# keyInput.net
KiCad netlist of a schematic drawn in Altium Designer
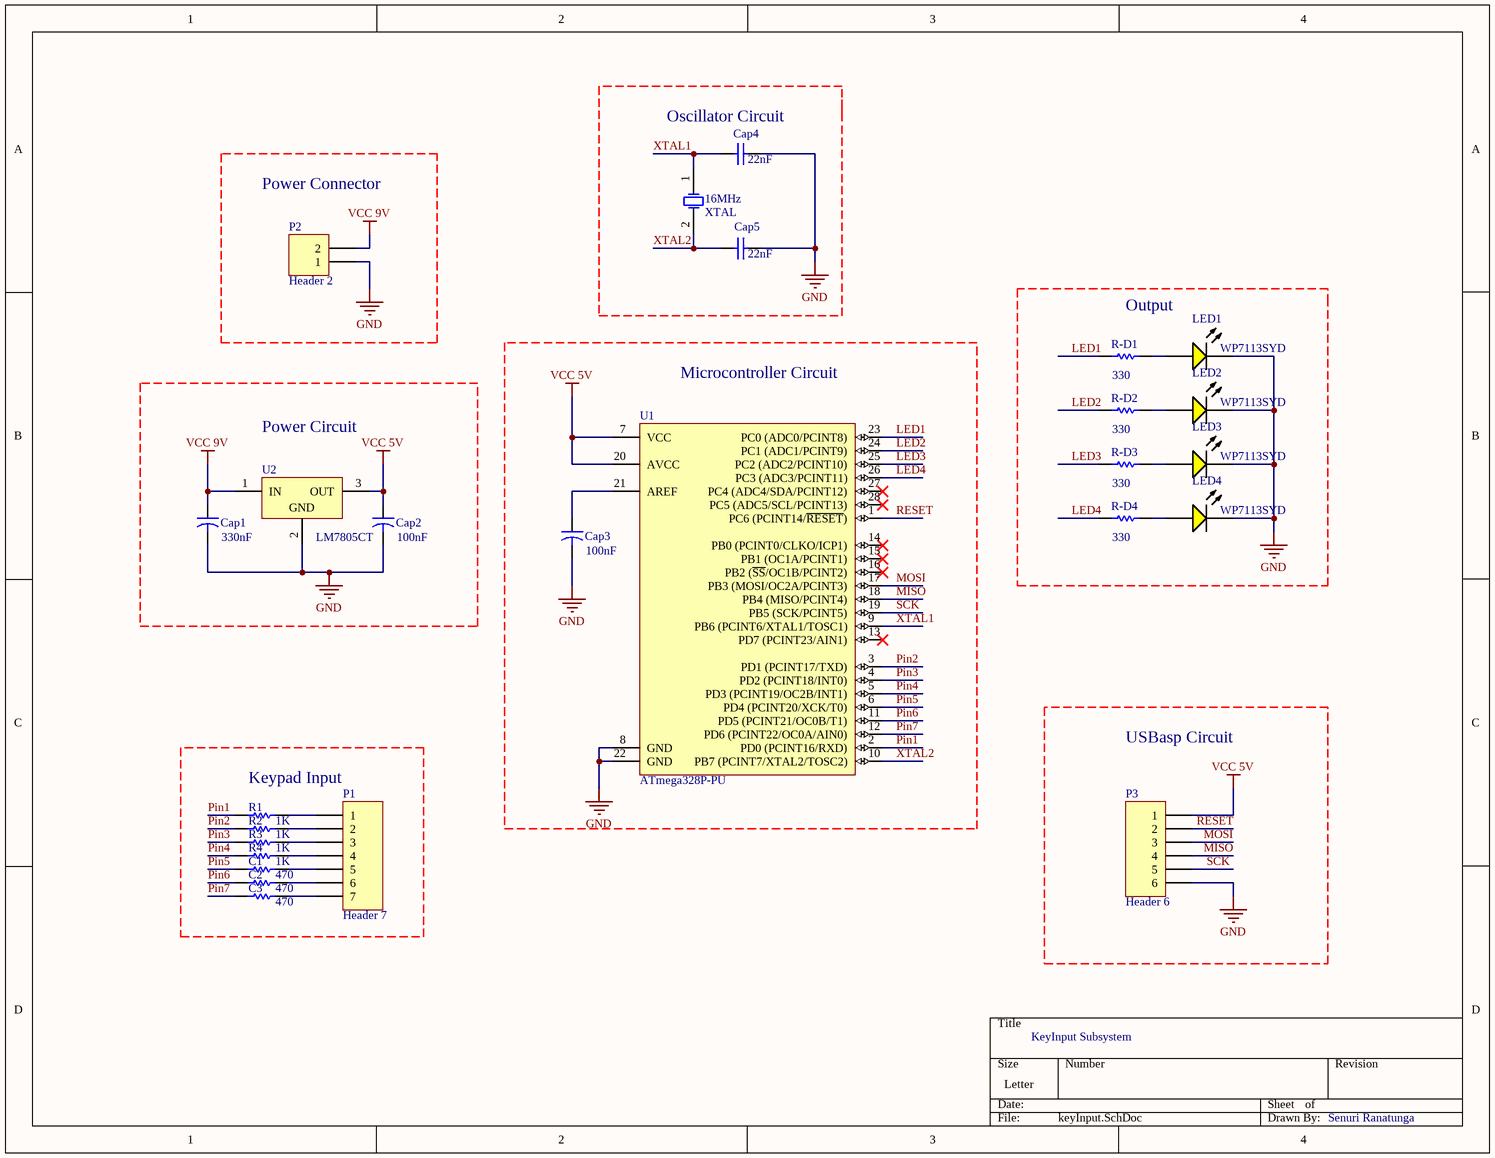
[diagram p0: keyInput.SchDoc]

(export (version "E")
  (design (tool "Eeschema 10.0.6"))
  (components
    (comp (ref "16MHz")
      (value "XTAL")
      (footprint "R38")
      (description "Crystal Oscillator")
      (fields (field (name "PUBLISHER") "Altium Limited"))
      (libsource (lib "Miscellaneous Devices") (part "XTAL"))
    )
    (comp (ref "C1")
      (value "470")
      (footprint "AXIAL-0.3")
      (description "Resistor")
      (fields (field (name "PUBLISHER") "Altium Limited"))
      (libsource (lib "Miscellaneous Devices") (part "Res1"))
    )
    (comp (ref "C2")
      (value "470")
      (footprint "AXIAL-0.3")
      (description "Resistor")
      (fields (field (name "PUBLISHER") "Altium Limited"))
      (libsource (lib "Miscellaneous Devices") (part "Res1"))
    )
    (comp (ref "C3")
      (value "470")
      (footprint "AXIAL-0.3")
      (description "Resistor")
      (fields (field (name "PUBLISHER") "Altium Limited"))
      (libsource (lib "Miscellaneous Devices") (part "Res1"))
    )
    (comp (ref "Cap1")
      (value "330nF")
      (footprint "CAPR5-4X5")
      (description "Capacitor")
      (fields (field (name "PUBLISHER") "Altium Limited"))
      (libsource (lib "Miscellaneous Devices") (part "Cap2"))
    )
    (comp (ref "Cap2")
      (value "100nF")
      (footprint "CAPR5-4X5")
      (description "Capacitor")
      (fields (field (name "PUBLISHER") "Altium Limited"))
      (libsource (lib "Miscellaneous Devices") (part "Cap2"))
    )
    (comp (ref "Cap3")
      (value "100nF")
      (footprint "CAPR5-4X5")
      (description "Capacitor")
      (fields (field (name "PUBLISHER") "Altium Limited"))
      (libsource (lib "Miscellaneous Devices") (part "Cap2"))
    )
    (comp (ref "Cap4")
      (value "22nF")
      (footprint "RAD-0.3")
      (description "Capacitor")
      (fields (field (name "PUBLISHER") "Altium Limited"))
      (libsource (lib "Miscellaneous Devices") (part "Cap"))
    )
    (comp (ref "Cap5")
      (value "22nF")
      (footprint "RAD-0.3")
      (description "Capacitor")
      (fields (field (name "PUBLISHER") "Altium Limited"))
      (libsource (lib "Miscellaneous Devices") (part "Cap"))
    )
    (comp (ref "LED1")
      (value "WP7113SYD")
      (footprint "KING-WP7113SYD_V")
      (description "The Super Bright Yellow Device, 2 V, -40 to 85 degC, 2-Pin THD, RoHS, Tape and Reel")
      (fields (field (name "TOLERANCE") "1%"))
      (libsource (lib "Altium Content Vault") (part "LED-YELLOW-AK-2"))
    )
    (comp (ref "LED2")
      (value "WP7113SYD")
      (footprint "KING-WP7113SYD_V")
      (description "The Super Bright Yellow Device, 2 V, -40 to 85 degC, 2-Pin THD, RoHS, Tape and Reel")
      (fields (field (name "TOLERANCE") "1%"))
      (libsource (lib "Altium Content Vault") (part "LED-YELLOW-AK-2"))
    )
    (comp (ref "LED3")
      (value "WP7113SYD")
      (footprint "KING-WP7113SYD_V")
      (description "The Super Bright Yellow Device, 2 V, -40 to 85 degC, 2-Pin THD, RoHS, Tape and Reel")
      (fields (field (name "TOLERANCE") "1%"))
      (libsource (lib "Altium Content Vault") (part "LED-YELLOW-AK-2"))
    )
    (comp (ref "LED4")
      (value "WP7113SYD")
      (footprint "KING-WP7113SYD_V")
      (description "The Super Bright Yellow Device, 2 V, -40 to 85 degC, 2-Pin THD, RoHS, Tape and Reel")
      (fields (field (name "TOLERANCE") "1%"))
      (libsource (lib "Altium Content Vault") (part "LED-YELLOW-AK-2"))
    )
    (comp (ref "P1")
      (value "Header 7")
      (footprint "HDR1X7")
      (description "Header, 7-Pin")
      (fields (field (name "PUBLISHER") "Altium Limited"))
      (libsource (lib "Miscellaneous Connectors") (part "Header 7"))
    )
    (comp (ref "P2")
      (value "Header 2")
      (footprint "HDR1X2")
      (description "Header, 2-Pin")
      (fields (field (name "PUBLISHER") "Altium Limited"))
      (libsource (lib "Miscellaneous Connectors") (part "Header 2"))
    )
    (comp (ref "P3")
      (value "Header 6")
      (footprint "HDR1X6")
      (description "Header, 6-Pin")
      (fields (field (name "PUBLISHER") "Altium Limited"))
      (libsource (lib "Miscellaneous Connectors") (part "Header 6"))
    )
    (comp (ref "R-D1")
      (value "330")
      (footprint "AXIAL-0.3")
      (description "Resistor")
      (fields (field (name "PUBLISHER") "Altium Limited"))
      (libsource (lib "Miscellaneous Devices") (part "Res1"))
    )
    (comp (ref "R-D2")
      (value "330")
      (footprint "AXIAL-0.3")
      (description "Resistor")
      (fields (field (name "PUBLISHER") "Altium Limited"))
      (libsource (lib "Miscellaneous Devices") (part "Res1"))
    )
    (comp (ref "R-D3")
      (value "330")
      (footprint "AXIAL-0.3")
      (description "Resistor")
      (fields (field (name "PUBLISHER") "Altium Limited"))
      (libsource (lib "Miscellaneous Devices") (part "Res1"))
    )
    (comp (ref "R-D4")
      (value "330")
      (footprint "AXIAL-0.3")
      (description "Resistor")
      (fields (field (name "PUBLISHER") "Altium Limited"))
      (libsource (lib "Miscellaneous Devices") (part "Res1"))
    )
    (comp (ref "R1")
      (value "1K")
      (footprint "AXIAL-0.3")
      (description "Resistor")
      (fields (field (name "PUBLISHER") "Altium Limited"))
      (libsource (lib "Miscellaneous Devices") (part "Res1"))
    )
    (comp (ref "R2")
      (value "1K")
      (footprint "AXIAL-0.3")
      (description "Resistor")
      (fields (field (name "PUBLISHER") "Altium Limited"))
      (libsource (lib "Miscellaneous Devices") (part "Res1"))
    )
    (comp (ref "R3")
      (value "1K")
      (footprint "AXIAL-0.3")
      (description "Resistor")
      (fields (field (name "PUBLISHER") "Altium Limited"))
      (libsource (lib "Miscellaneous Devices") (part "Res1"))
    )
    (comp (ref "R4")
      (value "1K")
      (footprint "AXIAL-0.3")
      (description "Resistor")
      (fields (field (name "PUBLISHER") "Altium Limited"))
      (libsource (lib "Miscellaneous Devices") (part "Res1"))
    )
    (comp (ref "U1")
      (value "ATmega328P-PU")
      (footprint "28P3")
      (libsource (lib "Altium Content Vault") (part "MC-8B-ATM48-IL28"))
    )
    (comp (ref "U2")
      (value "LM7805CT")
      (footprint "FAIR-TO-220-3")
      (description "Positive Voltage Regulator, 5 V, 1 A, -40 to 125 degC, 3-Pin TO-220, RoHS, Tube")
      (fields (field (name "MANUFACTURER") "FairchildSemiconductor"))
      (libsource (lib "Altium Content Vault") (part "FAIR-LM7805CT-TO220-3"))
    )
  )
  (nets
    (net (code "1") (name "/LED1") (class "Default")
      (node (ref "R-D1") (pin "1") (pinfunction "1_1") (pintype "passive"))
      (node (ref "U1") (pin "23") (pinfunction "PC0_(ADC0/PCINT8)_23") (pintype "bidirectional"))
    )
    (net (code "2") (name "/LED2") (class "Default")
      (node (ref "R-D2") (pin "1") (pinfunction "1_1") (pintype "passive"))
      (node (ref "U1") (pin "24") (pinfunction "PC1_(ADC1/PCINT9)_24") (pintype "bidirectional"))
    )
    (net (code "3") (name "/LED3") (class "Default")
      (node (ref "R-D3") (pin "1") (pinfunction "1_1") (pintype "passive"))
      (node (ref "U1") (pin "25") (pinfunction "PC2_(ADC2/PCINT10)_25") (pintype "bidirectional"))
    )
    (net (code "4") (name "/LED4") (class "Default")
      (node (ref "R-D4") (pin "1") (pinfunction "1_1") (pintype "passive"))
      (node (ref "U1") (pin "26") (pinfunction "PC3_(ADC3/PCINT11)_26") (pintype "bidirectional"))
    )
    (net (code "5") (name "/MISO") (class "Default")
      (node (ref "P3") (pin "4") (pinfunction "4_4") (pintype "passive"))
      (node (ref "U1") (pin "18") (pinfunction "PB4_(MISO/PCINT4)_18") (pintype "bidirectional"))
    )
    (net (code "6") (name "/MOSI") (class "Default")
      (node (ref "P3") (pin "3") (pinfunction "3_3") (pintype "passive"))
      (node (ref "U1") (pin "17") (pinfunction "PB3_(MOSI/OC2A/PCINT3)_17") (pintype "bidirectional"))
    )
    (net (code "7") (name "/Pin1") (class "Default")
      (node (ref "R1") (pin "2") (pinfunction "2_2") (pintype "passive"))
      (node (ref "U1") (pin "2") (pinfunction "PD0_(PCINT16/RXD)_2") (pintype "bidirectional"))
    )
    (net (code "8") (name "/Pin2") (class "Default")
      (node (ref "R2") (pin "1") (pinfunction "1_1") (pintype "passive"))
      (node (ref "U1") (pin "3") (pinfunction "PD1_(PCINT17/TXD)_3") (pintype "bidirectional"))
    )
    (net (code "9") (name "/Pin3") (class "Default")
      (node (ref "R3") (pin "1") (pinfunction "1_1") (pintype "passive"))
      (node (ref "U1") (pin "4") (pinfunction "PD2_(PCINT18/INT0)_4") (pintype "bidirectional"))
    )
    (net (code "10") (name "/Pin4") (class "Default")
      (node (ref "R4") (pin "2") (pinfunction "2_2") (pintype "passive"))
      (node (ref "U1") (pin "5") (pinfunction "PD3_(PCINT19/OC2B/INT1)_5") (pintype "bidirectional"))
    )
    (net (code "11") (name "/Pin5") (class "Default")
      (node (ref "C1") (pin "1") (pinfunction "1_1") (pintype "passive"))
      (node (ref "U1") (pin "6") (pinfunction "PD4_(PCINT20/XCK/T0)_6") (pintype "bidirectional"))
    )
    (net (code "12") (name "/Pin6") (class "Default")
      (node (ref "C2") (pin "1") (pinfunction "1_1") (pintype "passive"))
      (node (ref "U1") (pin "11") (pinfunction "PD5_(PCINT21/OC0B/T1)_11") (pintype "bidirectional"))
    )
    (net (code "13") (name "/Pin7") (class "Default")
      (node (ref "C3") (pin "1") (pinfunction "1_1") (pintype "passive"))
      (node (ref "U1") (pin "12") (pinfunction "PD6_(PCINT22/OC0A/AIN0)_12") (pintype "bidirectional"))
    )
    (net (code "14") (name "/RESET") (class "Default")
      (node (ref "P3") (pin "2") (pinfunction "2_2") (pintype "passive"))
      (node (ref "U1") (pin "1") (pinfunction "PC6_(PCINT14/~{RESET})_1") (pintype "bidirectional"))
    )
    (net (code "15") (name "/SCK") (class "Default")
      (node (ref "P3") (pin "5") (pinfunction "5_5") (pintype "passive"))
      (node (ref "U1") (pin "19") (pinfunction "PB5_(SCK/PCINT5)_19") (pintype "bidirectional"))
    )
    (net (code "16") (name "/XTAL1") (class "Default")
      (node (ref "16MHz") (pin "1") (pinfunction "OSC1_1") (pintype "passive"))
      (node (ref "Cap4") (pin "1") (pinfunction "1_1") (pintype "passive"))
      (node (ref "U1") (pin "9") (pinfunction "PB6_(PCINT6/XTAL1/TOSC1)_9") (pintype "bidirectional"))
    )
    (net (code "17") (name "/XTAL2") (class "Default")
      (node (ref "16MHz") (pin "2") (pinfunction "OSC2_2") (pintype "passive"))
      (node (ref "Cap5") (pin "1") (pinfunction "1_1") (pintype "passive"))
      (node (ref "U1") (pin "10") (pinfunction "PB7_(PCINT7/XTAL2/TOSC2)_10") (pintype "bidirectional"))
    )
    (net (code "18") (name "GND") (class "Default")
      (node (ref "Cap1") (pin "2") (pinfunction "2_2") (pintype "passive"))
      (node (ref "Cap2") (pin "2") (pinfunction "2_2") (pintype "passive"))
      (node (ref "Cap3") (pin "2") (pinfunction "2_2") (pintype "passive"))
      (node (ref "Cap4") (pin "2") (pinfunction "2_2") (pintype "passive"))
      (node (ref "Cap5") (pin "2") (pinfunction "2_2") (pintype "passive"))
      (node (ref "LED1") (pin "2") (pinfunction "K_2") (pintype "passive"))
      (node (ref "LED2") (pin "2") (pinfunction "K_2") (pintype "passive"))
      (node (ref "LED3") (pin "2") (pinfunction "K_2") (pintype "passive"))
      (node (ref "LED4") (pin "2") (pinfunction "K_2") (pintype "passive"))
      (node (ref "P2") (pin "1") (pinfunction "1_1") (pintype "passive"))
      (node (ref "P3") (pin "6") (pinfunction "6_6") (pintype "passive"))
      (node (ref "U1") (pin "22") (pinfunction "GND_22") (pintype "power_in"))
      (node (ref "U1") (pin "8") (pinfunction "GND_8") (pintype "power_in"))
      (node (ref "U2") (pin "2") (pinfunction "GND_2") (pintype "power_in"))
    )
    (net (code "19") (name "Net-(C1-Pad2)") (class "Default")
      (node (ref "C1") (pin "2") (pinfunction "2_2") (pintype "passive"))
      (node (ref "P1") (pin "5") (pinfunction "5_5") (pintype "passive"))
    )
    (net (code "20") (name "Net-(C2-Pad2)") (class "Default")
      (node (ref "C2") (pin "2") (pinfunction "2_2") (pintype "passive"))
      (node (ref "P1") (pin "6") (pinfunction "6_6") (pintype "passive"))
    )
    (net (code "21") (name "Net-(C3-Pad2)") (class "Default")
      (node (ref "C3") (pin "2") (pinfunction "2_2") (pintype "passive"))
      (node (ref "P1") (pin "7") (pinfunction "7_7") (pintype "passive"))
    )
    (net (code "22") (name "Net-(LED1-A)") (class "Default")
      (node (ref "LED1") (pin "1") (pinfunction "A_1") (pintype "passive"))
      (node (ref "R-D1") (pin "2") (pinfunction "2_2") (pintype "passive"))
    )
    (net (code "23") (name "Net-(LED2-A)") (class "Default")
      (node (ref "LED2") (pin "1") (pinfunction "A_1") (pintype "passive"))
      (node (ref "R-D2") (pin "2") (pinfunction "2_2") (pintype "passive"))
    )
    (net (code "24") (name "Net-(LED3-A)") (class "Default")
      (node (ref "LED3") (pin "1") (pinfunction "A_1") (pintype "passive"))
      (node (ref "R-D3") (pin "2") (pinfunction "2_2") (pintype "passive"))
    )
    (net (code "25") (name "Net-(LED4-A)") (class "Default")
      (node (ref "LED4") (pin "1") (pinfunction "A_1") (pintype "passive"))
      (node (ref "R-D4") (pin "2") (pinfunction "2_2") (pintype "passive"))
    )
    (net (code "26") (name "Net-(P1-Pad1)") (class "Default")
      (node (ref "P1") (pin "1") (pinfunction "1_1") (pintype "passive"))
      (node (ref "R1") (pin "1") (pinfunction "1_1") (pintype "passive"))
    )
    (net (code "27") (name "Net-(P1-Pad2)") (class "Default")
      (node (ref "P1") (pin "2") (pinfunction "2_2") (pintype "passive"))
      (node (ref "R2") (pin "2") (pinfunction "2_2") (pintype "passive"))
    )
    (net (code "28") (name "Net-(P1-Pad3)") (class "Default")
      (node (ref "P1") (pin "3") (pinfunction "3_3") (pintype "passive"))
      (node (ref "R3") (pin "2") (pinfunction "2_2") (pintype "passive"))
    )
    (net (code "29") (name "Net-(P1-Pad4)") (class "Default")
      (node (ref "P1") (pin "4") (pinfunction "4_4") (pintype "passive"))
      (node (ref "R4") (pin "1") (pinfunction "1_1") (pintype "passive"))
    )
    (net (code "30") (name "Net-(U1-AREF)") (class "Default")
      (node (ref "Cap3") (pin "1") (pinfunction "1_1") (pintype "passive"))
      (node (ref "U1") (pin "21") (pinfunction "AREF_21") (pintype "power_in"))
    )
    (net (code "31") (name "VCC 5V") (class "Default")
      (node (ref "Cap2") (pin "1") (pinfunction "1_1") (pintype "passive"))
      (node (ref "P3") (pin "1") (pinfunction "1_1") (pintype "passive"))
      (node (ref "U1") (pin "20") (pinfunction "AVCC_20") (pintype "power_in"))
      (node (ref "U1") (pin "7") (pinfunction "VCC_7") (pintype "power_in"))
      (node (ref "U2") (pin "3") (pinfunction "OUT_3") (pintype "power_in"))
    )
    (net (code "32") (name "VCC 9V") (class "Default")
      (node (ref "Cap1") (pin "1") (pinfunction "1_1") (pintype "passive"))
      (node (ref "P2") (pin "2") (pinfunction "2_2") (pintype "passive"))
      (node (ref "U2") (pin "1") (pinfunction "IN_1") (pintype "power_in"))
    )
    (net (code "33") (name "unconnected-(U1-PB0_(PCINT0{slash}CLKO{slash}ICP1)-Pad14)") (class "Default")
      (node (ref "U1") (pin "14") (pinfunction "PB0_(PCINT0/CLKO/ICP1)_14") (pintype "bidirectional+no_connect"))
    )
    (net (code "34") (name "unconnected-(U1-PB1_(OC1A{slash}PCINT1)-Pad15)") (class "Default")
      (node (ref "U1") (pin "15") (pinfunction "PB1_(OC1A/PCINT1)_15") (pintype "bidirectional+no_connect"))
    )
    (net (code "35") (name "unconnected-(U1-PB2_(~{SS}{slash}OC1B{slash}PCINT2)-Pad16)") (class "Default")
      (node (ref "U1") (pin "16") (pinfunction "PB2_(~{SS}/OC1B/PCINT2)_16") (pintype "bidirectional+no_connect"))
    )
    (net (code "36") (name "unconnected-(U1-PC4_(ADC4{slash}SDA{slash}PCINT12)-Pad27)") (class "Default")
      (node (ref "U1") (pin "27") (pinfunction "PC4_(ADC4/SDA/PCINT12)_27") (pintype "bidirectional+no_connect"))
    )
    (net (code "37") (name "unconnected-(U1-PC5_(ADC5{slash}SCL{slash}PCINT13)-Pad28)") (class "Default")
      (node (ref "U1") (pin "28") (pinfunction "PC5_(ADC5/SCL/PCINT13)_28") (pintype "bidirectional+no_connect"))
    )
    (net (code "38") (name "unconnected-(U1-PD7_(PCINT23{slash}AIN1)-Pad13)") (class "Default")
      (node (ref "U1") (pin "13") (pinfunction "PD7_(PCINT23/AIN1)_13") (pintype "bidirectional+no_connect"))
    )
  )
)
